# HV-DST.net
KiCad netlist of a schematic drawn in EAGLE
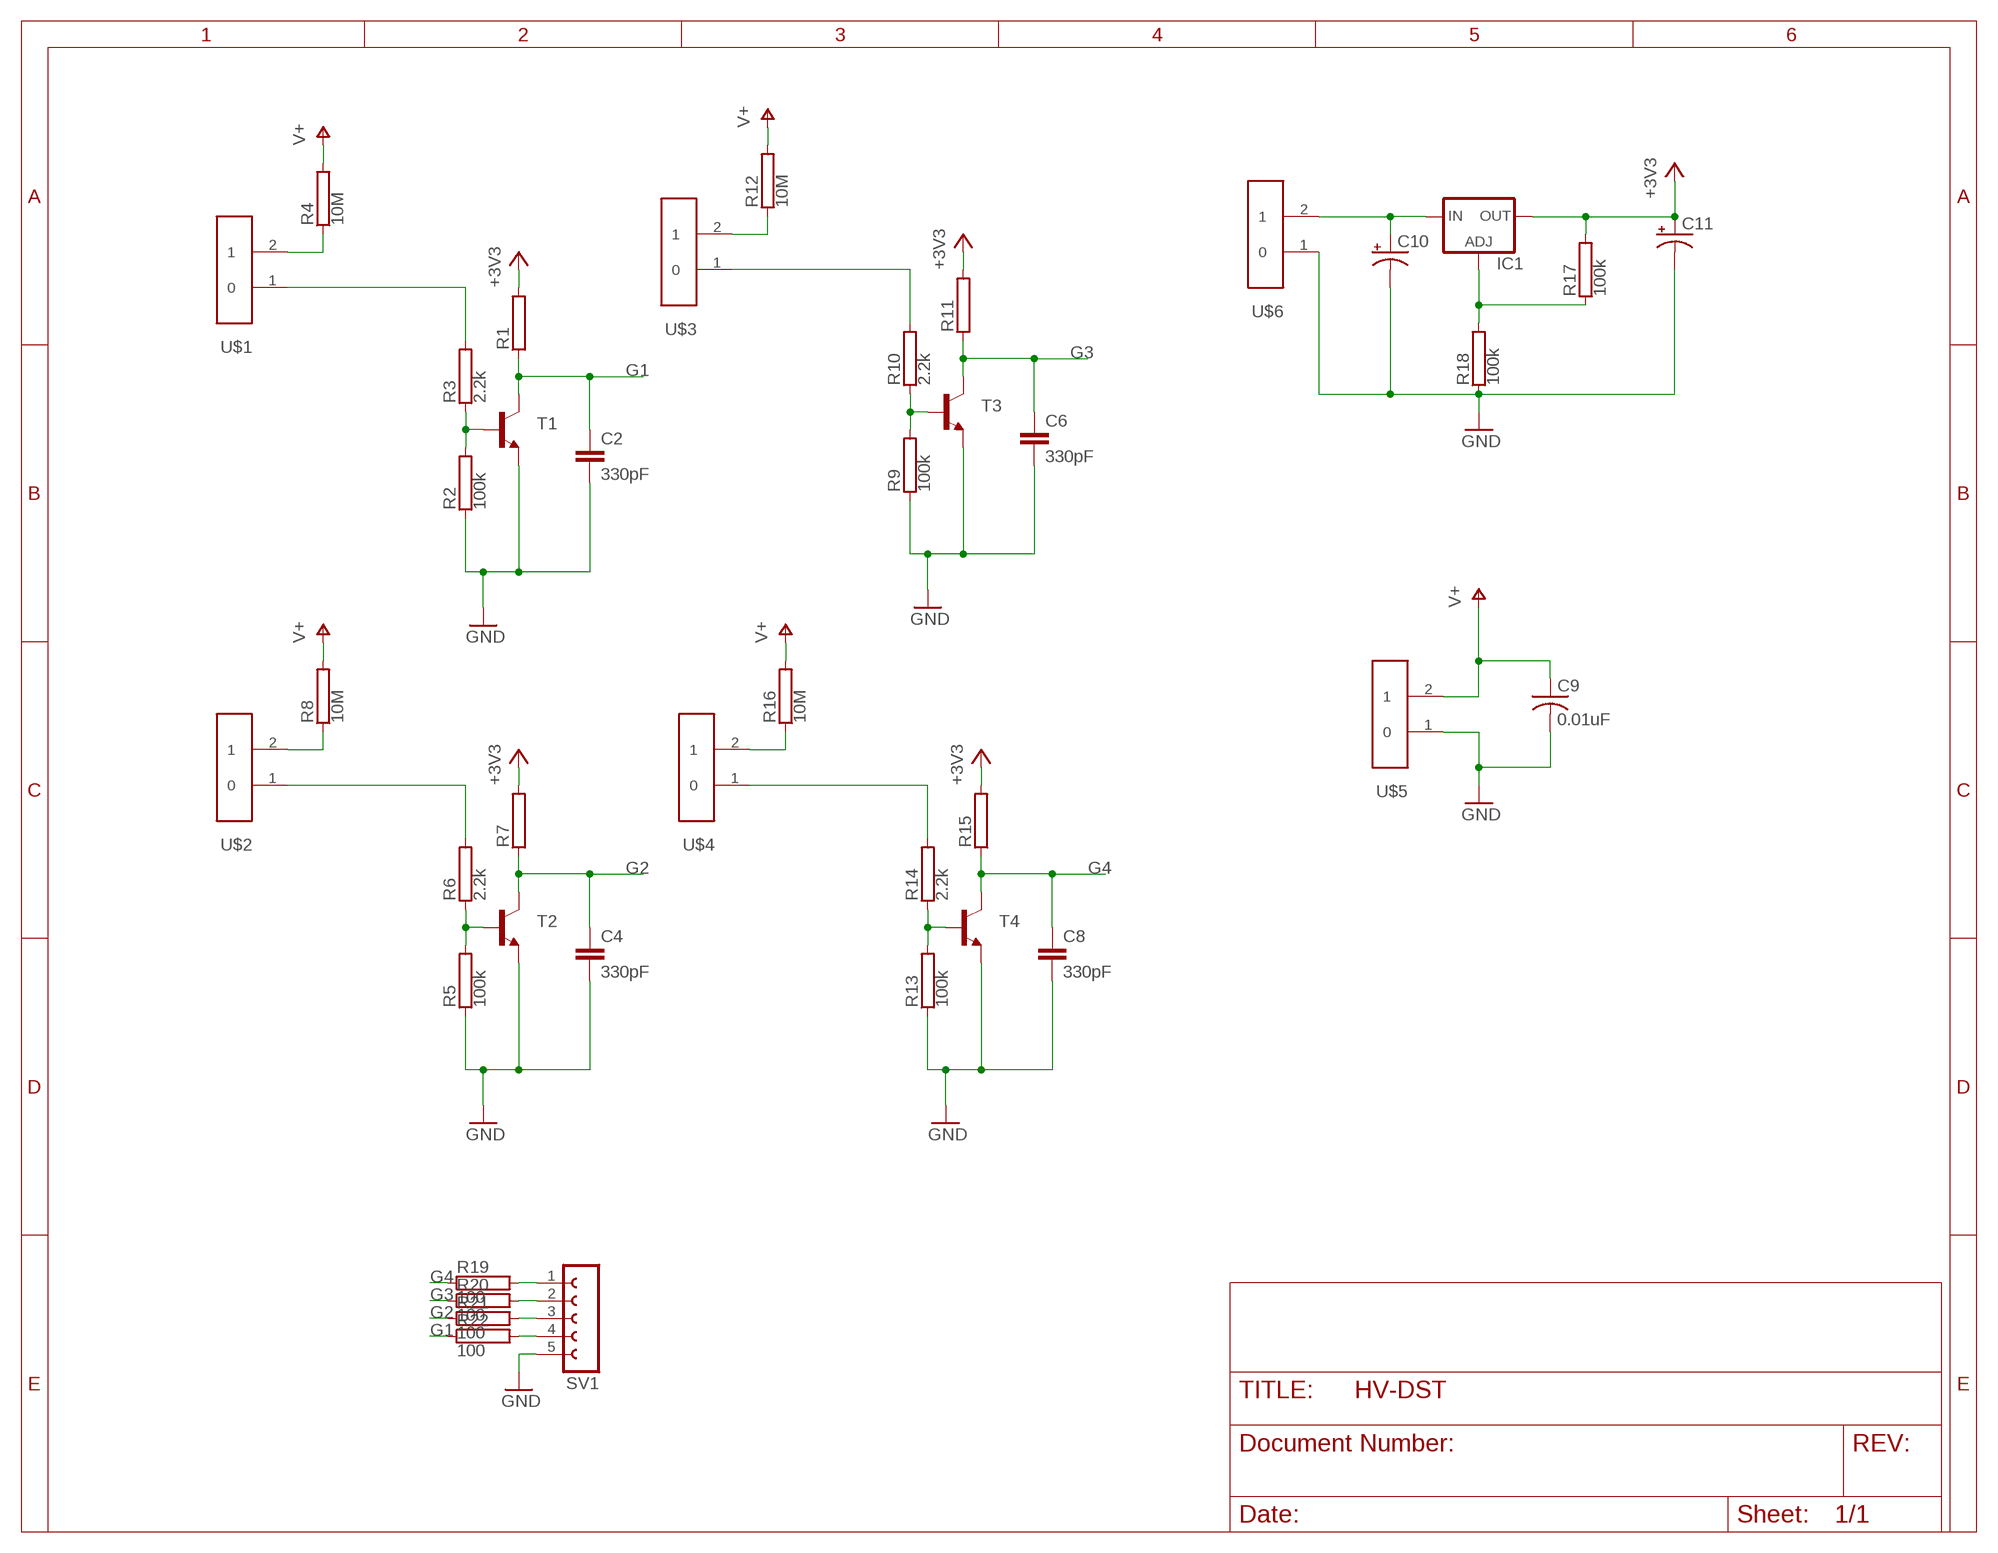
[diagram p0: schematic, sheet 1]

(export (version "E")
  (design (tool "Eeschema 10.0.6"))
  (components
    (comp (ref "C2")
      (value "330pF")
      (footprint "eagle-import:C2.5-2")
      (libsource (lib "eagle-import") (part "C2.5/2"))
    )
    (comp (ref "C4")
      (value "330pF")
      (footprint "eagle-import:C2.5-2")
      (libsource (lib "eagle-import") (part "C2.5/2"))
    )
    (comp (ref "C6")
      (value "330pF")
      (footprint "eagle-import:C2.5-2")
      (libsource (lib "eagle-import") (part "C2.5/2"))
    )
    (comp (ref "C8")
      (value "330pF")
      (footprint "eagle-import:C2.5-2")
      (libsource (lib "eagle-import") (part "C2.5/2"))
    )
    (comp (ref "C9")
      (value "0.01uF")
      (footprint "eagle-import:C075-032X103")
      (libsource (lib "eagle-import") (part "C-US075-032X103"))
    )
    (comp (ref "C10")
      (value "CPOL-USE2.5-5")
      (footprint "eagle-import:E2,5-5")
      (libsource (lib "eagle-import") (part "CPOL-USE2.5-5"))
    )
    (comp (ref "C11")
      (value "CPOL-USE2.5-5")
      (footprint "eagle-import:E2,5-5")
      (libsource (lib "eagle-import") (part "CPOL-USE2.5-5"))
    )
    (comp (ref "IC1")
      (value "LM317TS")
      (footprint "eagle-import:317TS")
      (libsource (lib "eagle-import") (part "LM317TS"))
    )
    (comp (ref "R1")
      (value "RRS1/4")
      (footprint "eagle-import:RS1_4")
      (fields (field (name "MF") "OHMITE") (field (name "MPN") "RRS1K0"))
      (libsource (lib "eagle-import") (part "RRS1/4"))
    )
    (comp (ref "R2")
      (value "100k")
      (footprint "eagle-import:RS1_4")
      (fields (field (name "MF") "OHMITE") (field (name "MPN") "RRS1K0"))
      (libsource (lib "eagle-import") (part "RRS1/4"))
    )
    (comp (ref "R3")
      (value "2.2k")
      (footprint "eagle-import:RS1_4")
      (fields (field (name "MF") "OHMITE") (field (name "MPN") "RRS1K0"))
      (libsource (lib "eagle-import") (part "RRS1/4"))
    )
    (comp (ref "R4")
      (value "10M")
      (footprint "eagle-import:RS1_4")
      (fields (field (name "MF") "OHMITE") (field (name "MPN") "RRS1K0"))
      (libsource (lib "eagle-import") (part "RRS1/4"))
    )
    (comp (ref "R5")
      (value "100k")
      (footprint "eagle-import:RS1_4")
      (fields (field (name "MF") "OHMITE") (field (name "MPN") "RRS1K0"))
      (libsource (lib "eagle-import") (part "RRS1/4"))
    )
    (comp (ref "R6")
      (value "2.2k")
      (footprint "eagle-import:RS1_4")
      (fields (field (name "MF") "OHMITE") (field (name "MPN") "RRS1K0"))
      (libsource (lib "eagle-import") (part "RRS1/4"))
    )
    (comp (ref "R7")
      (value "RRS1/4")
      (footprint "eagle-import:RS1_4")
      (fields (field (name "MF") "OHMITE") (field (name "MPN") "RRS1K0"))
      (libsource (lib "eagle-import") (part "RRS1/4"))
    )
    (comp (ref "R8")
      (value "10M")
      (footprint "eagle-import:RS1_4")
      (fields (field (name "MF") "OHMITE") (field (name "MPN") "RRS1K0"))
      (libsource (lib "eagle-import") (part "RRS1/4"))
    )
    (comp (ref "R9")
      (value "100k")
      (footprint "eagle-import:RS1_4")
      (fields (field (name "MF") "OHMITE") (field (name "MPN") "RRS1K0"))
      (libsource (lib "eagle-import") (part "RRS1/4"))
    )
    (comp (ref "R10")
      (value "2.2k")
      (footprint "eagle-import:RS1_4")
      (fields (field (name "MF") "OHMITE") (field (name "MPN") "RRS1K0"))
      (libsource (lib "eagle-import") (part "RRS1/4"))
    )
    (comp (ref "R11")
      (value "RRS1/4")
      (footprint "eagle-import:RS1_4")
      (fields (field (name "MF") "OHMITE") (field (name "MPN") "RRS1K0"))
      (libsource (lib "eagle-import") (part "RRS1/4"))
    )
    (comp (ref "R12")
      (value "10M")
      (footprint "eagle-import:RS1_4")
      (fields (field (name "MF") "OHMITE") (field (name "MPN") "RRS1K0"))
      (libsource (lib "eagle-import") (part "RRS1/4"))
    )
    (comp (ref "R13")
      (value "100k")
      (footprint "eagle-import:RS1_4")
      (fields (field (name "MF") "OHMITE") (field (name "MPN") "RRS1K0"))
      (libsource (lib "eagle-import") (part "RRS1/4"))
    )
    (comp (ref "R14")
      (value "2.2k")
      (footprint "eagle-import:RS1_4")
      (fields (field (name "MF") "OHMITE") (field (name "MPN") "RRS1K0"))
      (libsource (lib "eagle-import") (part "RRS1/4"))
    )
    (comp (ref "R15")
      (value "RRS1/4")
      (footprint "eagle-import:RS1_4")
      (fields (field (name "MF") "OHMITE") (field (name "MPN") "RRS1K0"))
      (libsource (lib "eagle-import") (part "RRS1/4"))
    )
    (comp (ref "R16")
      (value "10M")
      (footprint "eagle-import:RS1_4")
      (fields (field (name "MF") "OHMITE") (field (name "MPN") "RRS1K0"))
      (libsource (lib "eagle-import") (part "RRS1/4"))
    )
    (comp (ref "R17")
      (value "100k")
      (footprint "eagle-import:RS1_4")
      (fields (field (name "MF") "OHMITE") (field (name "MPN") "RRS1K0"))
      (libsource (lib "eagle-import") (part "RRS1/4"))
    )
    (comp (ref "R18")
      (value "100k")
      (footprint "eagle-import:RS1_4")
      (fields (field (name "MF") "OHMITE") (field (name "MPN") "RRS1K0"))
      (libsource (lib "eagle-import") (part "RRS1/4"))
    )
    (comp (ref "R19")
      (value "100")
      (footprint "eagle-import:RS1_4")
      (fields (field (name "MF") "OHMITE") (field (name "MPN") "RRS1K0"))
      (libsource (lib "eagle-import") (part "RRS1/4"))
    )
    (comp (ref "R20")
      (value "100")
      (footprint "eagle-import:RS1_4")
      (fields (field (name "MF") "OHMITE") (field (name "MPN") "RRS1K0"))
      (libsource (lib "eagle-import") (part "RRS1/4"))
    )
    (comp (ref "R21")
      (value "100")
      (footprint "eagle-import:RS1_4")
      (fields (field (name "MF") "OHMITE") (field (name "MPN") "RRS1K0"))
      (libsource (lib "eagle-import") (part "RRS1/4"))
    )
    (comp (ref "R22")
      (value "100")
      (footprint "eagle-import:RS1_4")
      (fields (field (name "MF") "OHMITE") (field (name "MPN") "RRS1K0"))
      (libsource (lib "eagle-import") (part "RRS1/4"))
    )
    (comp (ref "SV1")
      (value "FE05-1")
      (footprint "eagle-import:FE05-1")
      (libsource (lib "eagle-import") (part "FE05-1"))
    )
    (comp (ref "T1")
      (value "2N5551-NPN-TO92-CBE")
      (footprint "eagle-import:TO92-CBE")
      (libsource (lib "eagle-import") (part "-NPN-TO92-CBE2N5551"))
    )
    (comp (ref "T2")
      (value "2N5551-NPN-TO92-CBE")
      (footprint "eagle-import:TO92-CBE")
      (libsource (lib "eagle-import") (part "-NPN-TO92-CBE2N5551"))
    )
    (comp (ref "T3")
      (value "2N5551-NPN-TO92-CBE")
      (footprint "eagle-import:TO92-CBE")
      (libsource (lib "eagle-import") (part "-NPN-TO92-CBE2N5551"))
    )
    (comp (ref "T4")
      (value "2N5551-NPN-TO92-CBE")
      (footprint "eagle-import:TO92-CBE")
      (libsource (lib "eagle-import") (part "-NPN-TO92-CBE2N5551"))
    )
    (comp (ref "U$1")
      (value "ED2609")
      (footprint "eagle-import:ED2609")
      (libsource (lib "eagle-import") (part "ED2609"))
    )
    (comp (ref "U$2")
      (value "ED2609")
      (footprint "eagle-import:ED2609")
      (libsource (lib "eagle-import") (part "ED2609"))
    )
    (comp (ref "U$3")
      (value "ED2609")
      (footprint "eagle-import:ED2609")
      (libsource (lib "eagle-import") (part "ED2609"))
    )
    (comp (ref "U$4")
      (value "ED2609")
      (footprint "eagle-import:ED2609")
      (libsource (lib "eagle-import") (part "ED2609"))
    )
    (comp (ref "U$5")
      (value "ED2609")
      (footprint "eagle-import:ED2609")
      (libsource (lib "eagle-import") (part "ED2609"))
    )
    (comp (ref "U$6")
      (value "ED2609")
      (footprint "eagle-import:ED2609")
      (libsource (lib "eagle-import") (part "ED2609"))
    )
  )
  (nets
    (net (code "1") (name "+3V3") (class "Default")
      (node (ref "C11") (pin "+") (pinfunction "+_+") (pintype "passive"))
      (node (ref "IC1") (pin "2") (pinfunction "OUT_2") (pintype "passive"))
      (node (ref "R1") (pin "2") (pinfunction "2_2") (pintype "passive"))
      (node (ref "R11") (pin "2") (pinfunction "2_2") (pintype "passive"))
      (node (ref "R15") (pin "2") (pinfunction "2_2") (pintype "passive"))
      (node (ref "R17") (pin "2") (pinfunction "2_2") (pintype "passive"))
      (node (ref "R7") (pin "2") (pinfunction "2_2") (pintype "passive"))
    )
    (net (code "2") (name "/G1") (class "Default")
      (node (ref "C2") (pin "1") (pinfunction "1_1") (pintype "passive"))
      (node (ref "R1") (pin "1") (pinfunction "1_1") (pintype "passive"))
      (node (ref "R22") (pin "1") (pinfunction "1_1") (pintype "passive"))
      (node (ref "T1") (pin "C") (pinfunction "C_C") (pintype "passive"))
    )
    (net (code "3") (name "/G2") (class "Default")
      (node (ref "C4") (pin "1") (pinfunction "1_1") (pintype "passive"))
      (node (ref "R21") (pin "1") (pinfunction "1_1") (pintype "passive"))
      (node (ref "R7") (pin "1") (pinfunction "1_1") (pintype "passive"))
      (node (ref "T2") (pin "C") (pinfunction "C_C") (pintype "passive"))
    )
    (net (code "4") (name "/G3") (class "Default")
      (node (ref "C6") (pin "1") (pinfunction "1_1") (pintype "passive"))
      (node (ref "R11") (pin "1") (pinfunction "1_1") (pintype "passive"))
      (node (ref "R20") (pin "1") (pinfunction "1_1") (pintype "passive"))
      (node (ref "T3") (pin "C") (pinfunction "C_C") (pintype "passive"))
    )
    (net (code "5") (name "/G4") (class "Default")
      (node (ref "C8") (pin "1") (pinfunction "1_1") (pintype "passive"))
      (node (ref "R15") (pin "1") (pinfunction "1_1") (pintype "passive"))
      (node (ref "R19") (pin "1") (pinfunction "1_1") (pintype "passive"))
      (node (ref "T4") (pin "C") (pinfunction "C_C") (pintype "passive"))
    )
    (net (code "6") (name "GND") (class "Default")
      (node (ref "C10") (pin "-") (pinfunction "-_-") (pintype "passive"))
      (node (ref "C11") (pin "-") (pinfunction "-_-") (pintype "passive"))
      (node (ref "C2") (pin "2") (pinfunction "2_2") (pintype "passive"))
      (node (ref "C4") (pin "2") (pinfunction "2_2") (pintype "passive"))
      (node (ref "C6") (pin "2") (pinfunction "2_2") (pintype "passive"))
      (node (ref "C8") (pin "2") (pinfunction "2_2") (pintype "passive"))
      (node (ref "C9") (pin "2") (pinfunction "2_2") (pintype "passive"))
      (node (ref "R13") (pin "1") (pinfunction "1_1") (pintype "passive"))
      (node (ref "R18") (pin "1") (pinfunction "1_1") (pintype "passive"))
      (node (ref "R2") (pin "1") (pinfunction "1_1") (pintype "passive"))
      (node (ref "R5") (pin "1") (pinfunction "1_1") (pintype "passive"))
      (node (ref "R9") (pin "1") (pinfunction "1_1") (pintype "passive"))
      (node (ref "SV1") (pin "5") (pinfunction "5_5") (pintype "passive"))
      (node (ref "T1") (pin "E") (pinfunction "E_E") (pintype "passive"))
      (node (ref "T2") (pin "E") (pinfunction "E_E") (pintype "passive"))
      (node (ref "T3") (pin "E") (pinfunction "E_E") (pintype "passive"))
      (node (ref "T4") (pin "E") (pinfunction "E_E") (pintype "passive"))
      (node (ref "U$5") (pin "1") (pinfunction "0_1") (pintype "bidirectional"))
      (node (ref "U$6") (pin "1") (pinfunction "0_1") (pintype "bidirectional"))
    )
    (net (code "7") (name "Net-(IC1-ADJ)") (class "Default")
      (node (ref "IC1") (pin "1") (pinfunction "ADJ_1") (pintype "input"))
      (node (ref "R17") (pin "1") (pinfunction "1_1") (pintype "passive"))
      (node (ref "R18") (pin "2") (pinfunction "2_2") (pintype "passive"))
    )
    (net (code "8") (name "Net-(IC1-IN)") (class "Default")
      (node (ref "C10") (pin "+") (pinfunction "+_+") (pintype "passive"))
      (node (ref "IC1") (pin "3") (pinfunction "IN_3") (pintype "input"))
      (node (ref "U$6") (pin "2") (pinfunction "1_2") (pintype "bidirectional"))
    )
    (net (code "9") (name "Net-(R2-Pad2)") (class "Default")
      (node (ref "R2") (pin "2") (pinfunction "2_2") (pintype "passive"))
      (node (ref "R3") (pin "1") (pinfunction "1_1") (pintype "passive"))
      (node (ref "T1") (pin "B") (pinfunction "B_B") (pintype "passive"))
    )
    (net (code "10") (name "Net-(R5-Pad2)") (class "Default")
      (node (ref "R5") (pin "2") (pinfunction "2_2") (pintype "passive"))
      (node (ref "R6") (pin "1") (pinfunction "1_1") (pintype "passive"))
      (node (ref "T2") (pin "B") (pinfunction "B_B") (pintype "passive"))
    )
    (net (code "11") (name "Net-(R10-Pad1)") (class "Default")
      (node (ref "R10") (pin "1") (pinfunction "1_1") (pintype "passive"))
      (node (ref "R9") (pin "2") (pinfunction "2_2") (pintype "passive"))
      (node (ref "T3") (pin "B") (pinfunction "B_B") (pintype "passive"))
    )
    (net (code "12") (name "Net-(R13-Pad2)") (class "Default")
      (node (ref "R13") (pin "2") (pinfunction "2_2") (pintype "passive"))
      (node (ref "R14") (pin "1") (pinfunction "1_1") (pintype "passive"))
      (node (ref "T4") (pin "B") (pinfunction "B_B") (pintype "passive"))
    )
    (net (code "13") (name "Net-(R19-Pad2)") (class "Default")
      (node (ref "R19") (pin "2") (pinfunction "2_2") (pintype "passive"))
      (node (ref "SV1") (pin "1") (pinfunction "1_1") (pintype "passive"))
    )
    (net (code "14") (name "Net-(R20-Pad2)") (class "Default")
      (node (ref "R20") (pin "2") (pinfunction "2_2") (pintype "passive"))
      (node (ref "SV1") (pin "2") (pinfunction "2_2") (pintype "passive"))
    )
    (net (code "15") (name "Net-(R21-Pad2)") (class "Default")
      (node (ref "R21") (pin "2") (pinfunction "2_2") (pintype "passive"))
      (node (ref "SV1") (pin "3") (pinfunction "3_3") (pintype "passive"))
    )
    (net (code "16") (name "Net-(R22-Pad2)") (class "Default")
      (node (ref "R22") (pin "2") (pinfunction "2_2") (pintype "passive"))
      (node (ref "SV1") (pin "4") (pinfunction "4_4") (pintype "passive"))
    )
    (net (code "17") (name "Net-(U$1-0)") (class "Default")
      (node (ref "R3") (pin "2") (pinfunction "2_2") (pintype "passive"))
      (node (ref "U$1") (pin "1") (pinfunction "0_1") (pintype "bidirectional"))
    )
    (net (code "18") (name "Net-(U$1-1)") (class "Default")
      (node (ref "R4") (pin "1") (pinfunction "1_1") (pintype "passive"))
      (node (ref "U$1") (pin "2") (pinfunction "1_2") (pintype "bidirectional"))
    )
    (net (code "19") (name "Net-(U$2-0)") (class "Default")
      (node (ref "R6") (pin "2") (pinfunction "2_2") (pintype "passive"))
      (node (ref "U$2") (pin "1") (pinfunction "0_1") (pintype "bidirectional"))
    )
    (net (code "20") (name "Net-(U$2-1)") (class "Default")
      (node (ref "R8") (pin "1") (pinfunction "1_1") (pintype "passive"))
      (node (ref "U$2") (pin "2") (pinfunction "1_2") (pintype "bidirectional"))
    )
    (net (code "21") (name "Net-(U$3-0)") (class "Default")
      (node (ref "R10") (pin "2") (pinfunction "2_2") (pintype "passive"))
      (node (ref "U$3") (pin "1") (pinfunction "0_1") (pintype "bidirectional"))
    )
    (net (code "22") (name "Net-(U$3-1)") (class "Default")
      (node (ref "R12") (pin "1") (pinfunction "1_1") (pintype "passive"))
      (node (ref "U$3") (pin "2") (pinfunction "1_2") (pintype "bidirectional"))
    )
    (net (code "23") (name "Net-(U$4-0)") (class "Default")
      (node (ref "R14") (pin "2") (pinfunction "2_2") (pintype "passive"))
      (node (ref "U$4") (pin "1") (pinfunction "0_1") (pintype "bidirectional"))
    )
    (net (code "24") (name "Net-(U$4-1)") (class "Default")
      (node (ref "R16") (pin "1") (pinfunction "1_1") (pintype "passive"))
      (node (ref "U$4") (pin "2") (pinfunction "1_2") (pintype "bidirectional"))
    )
    (net (code "25") (name "V+") (class "Default")
      (node (ref "C9") (pin "1") (pinfunction "1_1") (pintype "passive"))
      (node (ref "R12") (pin "2") (pinfunction "2_2") (pintype "passive"))
      (node (ref "R16") (pin "2") (pinfunction "2_2") (pintype "passive"))
      (node (ref "R4") (pin "2") (pinfunction "2_2") (pintype "passive"))
      (node (ref "R8") (pin "2") (pinfunction "2_2") (pintype "passive"))
      (node (ref "U$5") (pin "2") (pinfunction "1_2") (pintype "bidirectional"))
    )
  )
)
